# CherryMX.net
KiCad netlist of a schematic drawn in Altium Designer
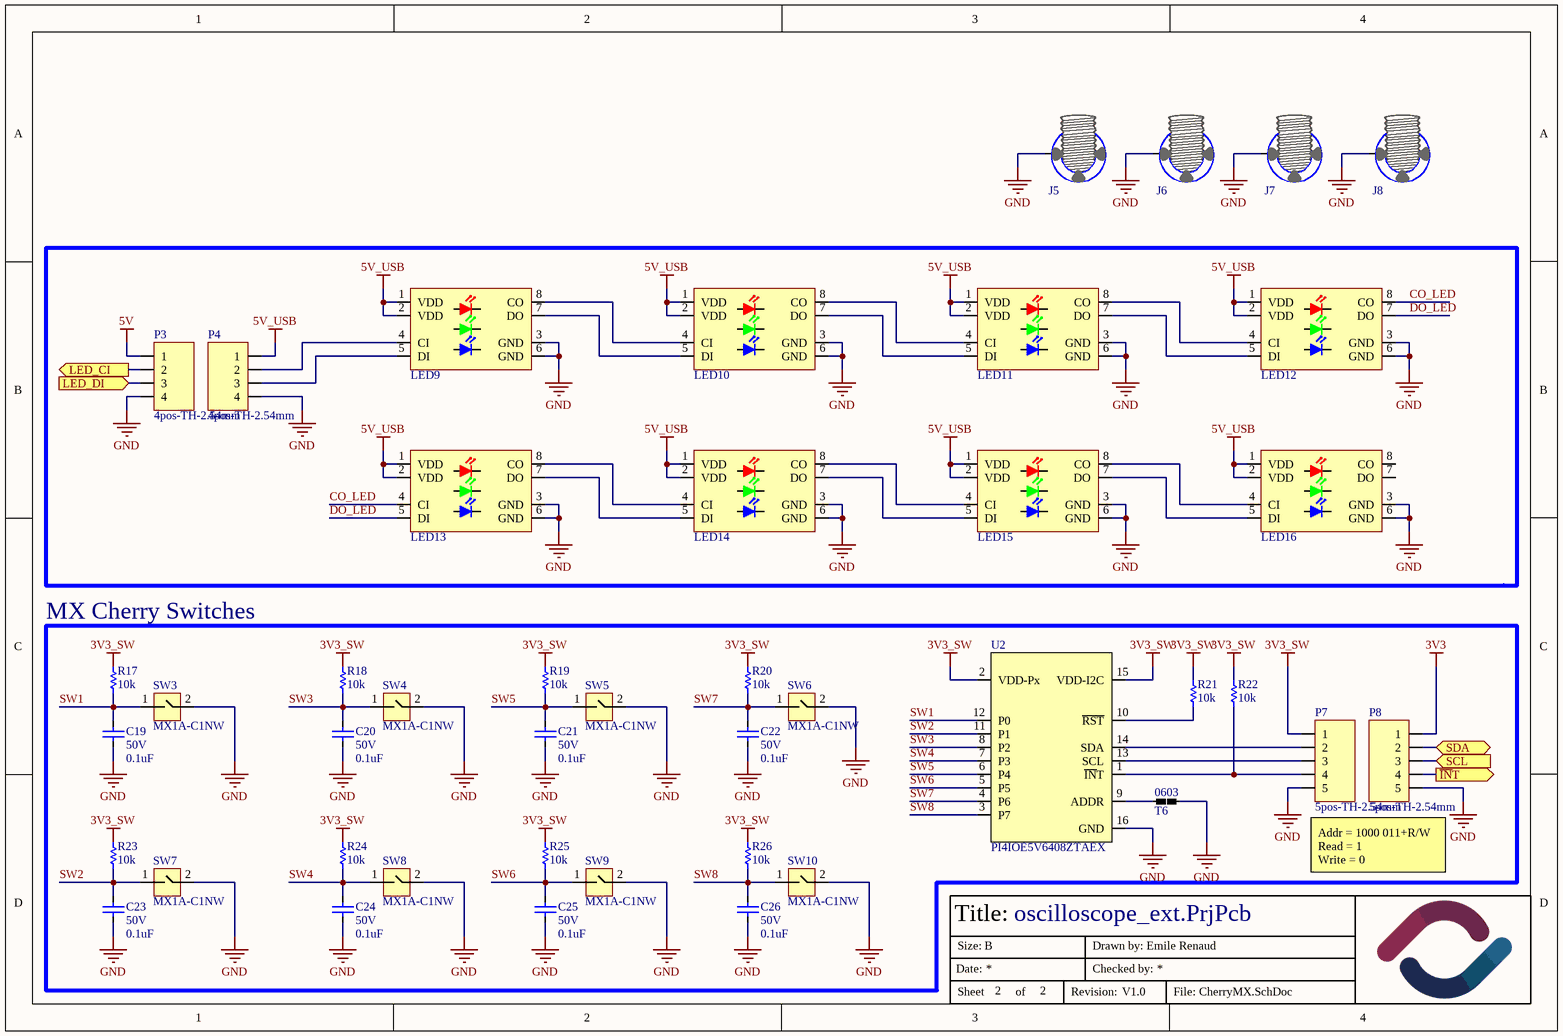
[diagram p0: CherryMX.SchDoc]

(export (version "E")
  (design (tool "Eeschema 10.0.6"))
  (components
    (comp (ref "C19")
      (value "0.1uF")
      (footprint "CAPACITOR-0603")
      (description "Capacitor-0603-0.1uF-50V-X7R")
      (fields (field (name "VOLT") "50V"))
      (libsource (lib "Capacitors") (part "Capacitor-0603-0.1uF-50V-X7R"))
    )
    (comp (ref "C20")
      (value "0.1uF")
      (footprint "CAPACITOR-0603")
      (description "Capacitor-0603-0.1uF-50V-X7R")
      (fields (field (name "VOLT") "50V"))
      (libsource (lib "Capacitors") (part "Capacitor-0603-0.1uF-50V-X7R"))
    )
    (comp (ref "C21")
      (value "0.1uF")
      (footprint "CAPACITOR-0603")
      (description "Capacitor-0603-0.1uF-50V-X7R")
      (fields (field (name "VOLT") "50V"))
      (libsource (lib "Capacitors") (part "Capacitor-0603-0.1uF-50V-X7R"))
    )
    (comp (ref "C22")
      (value "0.1uF")
      (footprint "CAPACITOR-0603")
      (description "Capacitor-0603-0.1uF-50V-X7R")
      (fields (field (name "VOLT") "50V"))
      (libsource (lib "Capacitors") (part "Capacitor-0603-0.1uF-50V-X7R"))
    )
    (comp (ref "C23")
      (value "0.1uF")
      (footprint "CAPACITOR-0603")
      (description "Capacitor-0603-0.1uF-50V-X7R")
      (fields (field (name "VOLT") "50V"))
      (libsource (lib "Capacitors") (part "Capacitor-0603-0.1uF-50V-X7R"))
    )
    (comp (ref "C24")
      (value "0.1uF")
      (footprint "CAPACITOR-0603")
      (description "Capacitor-0603-0.1uF-50V-X7R")
      (fields (field (name "VOLT") "50V"))
      (libsource (lib "Capacitors") (part "Capacitor-0603-0.1uF-50V-X7R"))
    )
    (comp (ref "C25")
      (value "0.1uF")
      (footprint "CAPACITOR-0603")
      (description "Capacitor-0603-0.1uF-50V-X7R")
      (fields (field (name "VOLT") "50V"))
      (libsource (lib "Capacitors") (part "Capacitor-0603-0.1uF-50V-X7R"))
    )
    (comp (ref "C26")
      (value "0.1uF")
      (footprint "CAPACITOR-0603")
      (description "Capacitor-0603-0.1uF-50V-X7R")
      (fields (field (name "VOLT") "50V"))
      (libsource (lib "Capacitors") (part "Capacitor-0603-0.1uF-50V-X7R"))
    )
    (comp (ref "J5")
      (value "hole")
      (footprint "HOLE-M2-Bolt")
      (description "Hole for M2 Bolt with 4mm pad")
      (libsource (lib "JumpersAndHoles") (part "Hole 2.3mm M2"))
    )
    (comp (ref "J6")
      (value "hole")
      (footprint "HOLE-M2-Bolt")
      (description "Hole for M2 Bolt with 4mm pad")
      (libsource (lib "JumpersAndHoles") (part "Hole 2.3mm M2"))
    )
    (comp (ref "J7")
      (value "hole")
      (footprint "HOLE-M2-Bolt")
      (description "Hole for M2 Bolt with 4mm pad")
      (libsource (lib "JumpersAndHoles") (part "Hole 2.3mm M2"))
    )
    (comp (ref "J8")
      (value "hole")
      (footprint "HOLE-M2-Bolt")
      (description "Hole for M2 Bolt with 4mm pad")
      (libsource (lib "JumpersAndHoles") (part "Hole 2.3mm M2"))
    )
    (comp (ref "LED9")
      (value "DotStar Micro")
      (footprint "LED_DOTSTAR")
      (libsource (lib "LEDs") (part "DotStar Micro"))
    )
    (comp (ref "LED10")
      (value "DotStar Micro")
      (footprint "LED_DOTSTAR")
      (libsource (lib "LEDs") (part "DotStar Micro"))
    )
    (comp (ref "LED11")
      (value "DotStar Micro")
      (footprint "LED_DOTSTAR")
      (libsource (lib "LEDs") (part "DotStar Micro"))
    )
    (comp (ref "LED12")
      (value "DotStar Micro")
      (footprint "LED_DOTSTAR")
      (libsource (lib "LEDs") (part "DotStar Micro"))
    )
    (comp (ref "LED13")
      (value "DotStar Micro")
      (footprint "LED_DOTSTAR")
      (libsource (lib "LEDs") (part "DotStar Micro"))
    )
    (comp (ref "LED14")
      (value "DotStar Micro")
      (footprint "LED_DOTSTAR")
      (libsource (lib "LEDs") (part "DotStar Micro"))
    )
    (comp (ref "LED15")
      (value "DotStar Micro")
      (footprint "LED_DOTSTAR")
      (libsource (lib "LEDs") (part "DotStar Micro"))
    )
    (comp (ref "LED16")
      (value "DotStar Micro")
      (footprint "LED_DOTSTAR")
      (libsource (lib "LEDs") (part "DotStar Micro"))
    )
    (comp (ref "P3")
      (value "4pos-TH-2.54mm")
      (footprint "HDR1X4")
      (description "4pos TH 2.54mm Header")
      (libsource (lib "") (part "4pos-TH-2.54mm_1"))
    )
    (comp (ref "P4")
      (value "4pos-TH-2.54mm")
      (footprint "HDR1X4")
      (description "4pos TH 2.54mm Header")
      (libsource (lib "Header") (part "4pos-TH-2.54mm"))
    )
    (comp (ref "P7")
      (value "5pos-TH-2.54mm")
      (footprint "HDR1X5")
      (description "5pos TH 2.54mm Header")
      (libsource (lib "") (part "5pos-TH-2.54mm_1"))
    )
    (comp (ref "P8")
      (value "5pos-TH-2.54mm")
      (footprint "HDR1X5")
      (description "5pos TH 2.54mm Header")
      (libsource (lib "Header") (part "5pos-TH-2.54mm"))
    )
    (comp (ref "R17")
      (value "10k")
      (footprint "Resistor-0603")
      (description "Resistor0603-10k")
      (fields (field (name "Comment") "SMT resistor"))
      (libsource (lib "Resistors") (part "Resistor0603-10k"))
    )
    (comp (ref "R18")
      (value "10k")
      (footprint "Resistor-0603")
      (description "Resistor0603-10k")
      (fields (field (name "Comment") "SMT resistor"))
      (libsource (lib "Resistors") (part "Resistor0603-10k"))
    )
    (comp (ref "R19")
      (value "10k")
      (footprint "Resistor-0603")
      (description "Resistor0603-10k")
      (fields (field (name "Comment") "SMT resistor"))
      (libsource (lib "Resistors") (part "Resistor0603-10k"))
    )
    (comp (ref "R20")
      (value "10k")
      (footprint "Resistor-0603")
      (description "Resistor0603-10k")
      (fields (field (name "Comment") "SMT resistor"))
      (libsource (lib "Resistors") (part "Resistor0603-10k"))
    )
    (comp (ref "R21")
      (value "10k")
      (footprint "Resistor-0603")
      (description "Resistor0603-10k")
      (fields (field (name "Comment") "SMT resistor"))
      (libsource (lib "Resistors") (part "Resistor0603-10k"))
    )
    (comp (ref "R22")
      (value "10k")
      (footprint "Resistor-0603")
      (description "Resistor0603-10k")
      (fields (field (name "Comment") "SMT resistor"))
      (libsource (lib "Resistors") (part "Resistor0603-10k"))
    )
    (comp (ref "R23")
      (value "10k")
      (footprint "Resistor-0603")
      (description "Resistor0603-10k")
      (fields (field (name "Comment") "SMT resistor"))
      (libsource (lib "Resistors") (part "Resistor0603-10k"))
    )
    (comp (ref "R24")
      (value "10k")
      (footprint "Resistor-0603")
      (description "Resistor0603-10k")
      (fields (field (name "Comment") "SMT resistor"))
      (libsource (lib "Resistors") (part "Resistor0603-10k"))
    )
    (comp (ref "R25")
      (value "10k")
      (footprint "Resistor-0603")
      (description "Resistor0603-10k")
      (fields (field (name "Comment") "SMT resistor"))
      (libsource (lib "Resistors") (part "Resistor0603-10k"))
    )
    (comp (ref "R26")
      (value "10k")
      (footprint "Resistor-0603")
      (description "Resistor0603-10k")
      (fields (field (name "Comment") "SMT resistor"))
      (libsource (lib "Resistors") (part "Resistor0603-10k"))
    )
    (comp (ref "SW3")
      (value "MX1A-C1NW")
      (footprint "MX2A-G1NB")
      (description "Pushbutton Switch SPST-NO Keyswitch Through Hole")
      (libsource (lib "Switches") (part "MX1A-C1NW"))
    )
    (comp (ref "SW4")
      (value "MX1A-C1NW")
      (footprint "MX2A-G1NB")
      (description "Pushbutton Switch SPST-NO Keyswitch Through Hole")
      (libsource (lib "Switches") (part "MX1A-C1NW"))
    )
    (comp (ref "SW5")
      (value "MX1A-C1NW")
      (footprint "MX2A-G1NB")
      (description "Pushbutton Switch SPST-NO Keyswitch Through Hole")
      (libsource (lib "Switches") (part "MX1A-C1NW"))
    )
    (comp (ref "SW6")
      (value "MX1A-C1NW")
      (footprint "MX2A-G1NB")
      (description "Pushbutton Switch SPST-NO Keyswitch Through Hole")
      (libsource (lib "Switches") (part "MX1A-C1NW"))
    )
    (comp (ref "SW7")
      (value "MX1A-C1NW")
      (footprint "MX2A-G1NB")
      (description "Pushbutton Switch SPST-NO Keyswitch Through Hole")
      (libsource (lib "Switches") (part "MX1A-C1NW"))
    )
    (comp (ref "SW8")
      (value "MX1A-C1NW")
      (footprint "MX2A-G1NB")
      (description "Pushbutton Switch SPST-NO Keyswitch Through Hole")
      (libsource (lib "Switches") (part "MX1A-C1NW"))
    )
    (comp (ref "SW9")
      (value "MX1A-C1NW")
      (footprint "MX2A-G1NB")
      (description "Pushbutton Switch SPST-NO Keyswitch Through Hole")
      (libsource (lib "Switches") (part "MX1A-C1NW"))
    )
    (comp (ref "SW10")
      (value "MX1A-C1NW")
      (footprint "MX2A-G1NB")
      (description "Pushbutton Switch SPST-NO Keyswitch Through Hole")
      (libsource (lib "Switches") (part "MX1A-C1NW"))
    )
    (comp (ref "T6")
      (value "NetTie_0603")
      (footprint "NetTie-0603-short")
      (libsource (lib "JumpersAndHoles") (part "NetTie_0603"))
    )
    (comp (ref "U2")
      (value "PI4IOE5V6408ZTAEX")
      (footprint "UQFN-16")
      (description "I/O Expander 8 I2C 1 MHz 16-UQFN (1.8x2.6)")
      (libsource (lib "IO-Expander") (part "PI4IOE5V6408ZTAEX"))
    )
  )
  (nets
    (net (code "1") (name "/CO_LED") (class "Default")
      (node (ref "LED12") (pin "8") (pinfunction "CO_8") (pintype "passive"))
      (node (ref "LED13") (pin "4") (pinfunction "CI_4") (pintype "passive"))
    )
    (net (code "2") (name "/DO_LED") (class "Default")
      (node (ref "LED12") (pin "7") (pinfunction "DO_7") (pintype "passive"))
      (node (ref "LED13") (pin "5") (pinfunction "DI_5") (pintype "passive"))
    )
    (net (code "3") (name "/LED_CI") (class "Default")
      (node (ref "P3") (pin "2") (pinfunction "2_2") (pintype "passive"))
    )
    (net (code "4") (name "/LED_DI") (class "Default")
      (node (ref "P3") (pin "3") (pinfunction "3_3") (pintype "passive"))
    )
    (net (code "5") (name "/SCL") (class "Default")
      (node (ref "P8") (pin "3") (pinfunction "3_3") (pintype "passive"))
    )
    (net (code "6") (name "/SDA") (class "Default")
      (node (ref "P8") (pin "2") (pinfunction "2_2") (pintype "passive"))
    )
    (net (code "7") (name "/SW1") (class "Default")
      (node (ref "C19") (pin "2") (pinfunction "2_2") (pintype "passive"))
      (node (ref "R17") (pin "1") (pinfunction "1_1") (pintype "passive"))
      (node (ref "SW3") (pin "1") (pinfunction "1_1") (pintype "passive"))
      (node (ref "U2") (pin "12") (pinfunction "P0_12") (pintype "passive"))
    )
    (net (code "8") (name "/SW2") (class "Default")
      (node (ref "C23") (pin "2") (pinfunction "2_2") (pintype "passive"))
      (node (ref "R23") (pin "1") (pinfunction "1_1") (pintype "passive"))
      (node (ref "SW7") (pin "1") (pinfunction "1_1") (pintype "passive"))
      (node (ref "U2") (pin "11") (pinfunction "P1_11") (pintype "passive"))
    )
    (net (code "9") (name "/SW3") (class "Default")
      (node (ref "C20") (pin "2") (pinfunction "2_2") (pintype "passive"))
      (node (ref "R18") (pin "1") (pinfunction "1_1") (pintype "passive"))
      (node (ref "SW4") (pin "1") (pinfunction "1_1") (pintype "passive"))
      (node (ref "U2") (pin "8") (pinfunction "P2_8") (pintype "passive"))
    )
    (net (code "10") (name "/SW4") (class "Default")
      (node (ref "C24") (pin "2") (pinfunction "2_2") (pintype "passive"))
      (node (ref "R24") (pin "1") (pinfunction "1_1") (pintype "passive"))
      (node (ref "SW8") (pin "1") (pinfunction "1_1") (pintype "passive"))
      (node (ref "U2") (pin "7") (pinfunction "P3_7") (pintype "passive"))
    )
    (net (code "11") (name "/SW5") (class "Default")
      (node (ref "C21") (pin "2") (pinfunction "2_2") (pintype "passive"))
      (node (ref "R19") (pin "1") (pinfunction "1_1") (pintype "passive"))
      (node (ref "SW5") (pin "1") (pinfunction "1_1") (pintype "passive"))
      (node (ref "U2") (pin "6") (pinfunction "P4_6") (pintype "passive"))
    )
    (net (code "12") (name "/SW6") (class "Default")
      (node (ref "C25") (pin "2") (pinfunction "2_2") (pintype "passive"))
      (node (ref "R25") (pin "1") (pinfunction "1_1") (pintype "passive"))
      (node (ref "SW9") (pin "1") (pinfunction "1_1") (pintype "passive"))
      (node (ref "U2") (pin "5") (pinfunction "P5_5") (pintype "passive"))
    )
    (net (code "13") (name "/SW7") (class "Default")
      (node (ref "C22") (pin "2") (pinfunction "2_2") (pintype "passive"))
      (node (ref "R20") (pin "1") (pinfunction "1_1") (pintype "passive"))
      (node (ref "SW6") (pin "1") (pinfunction "1_1") (pintype "passive"))
      (node (ref "U2") (pin "4") (pinfunction "P6_4") (pintype "passive"))
    )
    (net (code "14") (name "/SW8") (class "Default")
      (node (ref "C26") (pin "2") (pinfunction "2_2") (pintype "passive"))
      (node (ref "R26") (pin "1") (pinfunction "1_1") (pintype "passive"))
      (node (ref "SW10") (pin "1") (pinfunction "1_1") (pintype "passive"))
      (node (ref "U2") (pin "3") (pinfunction "P7_3") (pintype "passive"))
    )
    (net (code "15") (name "/~{IN}T") (class "Default")
      (node (ref "P8") (pin "4") (pinfunction "4_4") (pintype "passive"))
    )
    (net (code "16") (name "3V3") (class "Default")
      (node (ref "P8") (pin "1") (pinfunction "1_1") (pintype "passive"))
    )
    (net (code "17") (name "3V3_SW") (class "Default")
      (node (ref "P7") (pin "1") (pinfunction "1_1") (pintype "passive"))
      (node (ref "R17") (pin "2") (pinfunction "2_2") (pintype "passive"))
      (node (ref "R18") (pin "2") (pinfunction "2_2") (pintype "passive"))
      (node (ref "R19") (pin "2") (pinfunction "2_2") (pintype "passive"))
      (node (ref "R20") (pin "2") (pinfunction "2_2") (pintype "passive"))
      (node (ref "R21") (pin "2") (pinfunction "2_2") (pintype "passive"))
      (node (ref "R22") (pin "2") (pinfunction "2_2") (pintype "passive"))
      (node (ref "R23") (pin "2") (pinfunction "2_2") (pintype "passive"))
      (node (ref "R24") (pin "2") (pinfunction "2_2") (pintype "passive"))
      (node (ref "R25") (pin "2") (pinfunction "2_2") (pintype "passive"))
      (node (ref "R26") (pin "2") (pinfunction "2_2") (pintype "passive"))
      (node (ref "U2") (pin "15") (pinfunction "VDD-I2C_15") (pintype "passive"))
      (node (ref "U2") (pin "2") (pinfunction "VDD-Px_2") (pintype "passive"))
    )
    (net (code "18") (name "5V") (class "Default")
      (node (ref "P3") (pin "1") (pinfunction "1_1") (pintype "passive"))
    )
    (net (code "19") (name "5V_USB") (class "Default")
      (node (ref "LED10") (pin "1") (pinfunction "VDD_1") (pintype "passive"))
      (node (ref "LED10") (pin "2") (pinfunction "VDD_2") (pintype "passive"))
      (node (ref "LED11") (pin "1") (pinfunction "VDD_1") (pintype "passive"))
      (node (ref "LED11") (pin "2") (pinfunction "VDD_2") (pintype "passive"))
      (node (ref "LED12") (pin "1") (pinfunction "VDD_1") (pintype "passive"))
      (node (ref "LED12") (pin "2") (pinfunction "VDD_2") (pintype "passive"))
      (node (ref "LED13") (pin "1") (pinfunction "VDD_1") (pintype "passive"))
      (node (ref "LED13") (pin "2") (pinfunction "VDD_2") (pintype "passive"))
      (node (ref "LED14") (pin "1") (pinfunction "VDD_1") (pintype "passive"))
      (node (ref "LED14") (pin "2") (pinfunction "VDD_2") (pintype "passive"))
      (node (ref "LED15") (pin "1") (pinfunction "VDD_1") (pintype "passive"))
      (node (ref "LED15") (pin "2") (pinfunction "VDD_2") (pintype "passive"))
      (node (ref "LED16") (pin "1") (pinfunction "VDD_1") (pintype "passive"))
      (node (ref "LED16") (pin "2") (pinfunction "VDD_2") (pintype "passive"))
      (node (ref "LED9") (pin "1") (pinfunction "VDD_1") (pintype "passive"))
      (node (ref "LED9") (pin "2") (pinfunction "VDD_2") (pintype "passive"))
      (node (ref "P4") (pin "1") (pinfunction "1_1") (pintype "passive"))
    )
    (net (code "20") (name "GND") (class "Default")
      (node (ref "C19") (pin "1") (pinfunction "1_1") (pintype "passive"))
      (node (ref "C20") (pin "1") (pinfunction "1_1") (pintype "passive"))
      (node (ref "C21") (pin "1") (pinfunction "1_1") (pintype "passive"))
      (node (ref "C22") (pin "1") (pinfunction "1_1") (pintype "passive"))
      (node (ref "C23") (pin "1") (pinfunction "1_1") (pintype "passive"))
      (node (ref "C24") (pin "1") (pinfunction "1_1") (pintype "passive"))
      (node (ref "C25") (pin "1") (pinfunction "1_1") (pintype "passive"))
      (node (ref "C26") (pin "1") (pinfunction "1_1") (pintype "passive"))
      (node (ref "J5") (pin "1") (pinfunction "1_1") (pintype "passive"))
      (node (ref "J6") (pin "1") (pinfunction "1_1") (pintype "passive"))
      (node (ref "J7") (pin "1") (pinfunction "1_1") (pintype "passive"))
      (node (ref "J8") (pin "1") (pinfunction "1_1") (pintype "passive"))
      (node (ref "LED10") (pin "3") (pinfunction "GND_3") (pintype "passive"))
      (node (ref "LED10") (pin "6") (pinfunction "GND_6") (pintype "passive"))
      (node (ref "LED11") (pin "3") (pinfunction "GND_3") (pintype "passive"))
      (node (ref "LED11") (pin "6") (pinfunction "GND_6") (pintype "passive"))
      (node (ref "LED12") (pin "3") (pinfunction "GND_3") (pintype "passive"))
      (node (ref "LED12") (pin "6") (pinfunction "GND_6") (pintype "passive"))
      (node (ref "LED13") (pin "3") (pinfunction "GND_3") (pintype "passive"))
      (node (ref "LED13") (pin "6") (pinfunction "GND_6") (pintype "passive"))
      (node (ref "LED14") (pin "3") (pinfunction "GND_3") (pintype "passive"))
      (node (ref "LED14") (pin "6") (pinfunction "GND_6") (pintype "passive"))
      (node (ref "LED15") (pin "3") (pinfunction "GND_3") (pintype "passive"))
      (node (ref "LED15") (pin "6") (pinfunction "GND_6") (pintype "passive"))
      (node (ref "LED16") (pin "3") (pinfunction "GND_3") (pintype "passive"))
      (node (ref "LED16") (pin "6") (pinfunction "GND_6") (pintype "passive"))
      (node (ref "LED9") (pin "3") (pinfunction "GND_3") (pintype "passive"))
      (node (ref "LED9") (pin "6") (pinfunction "GND_6") (pintype "passive"))
      (node (ref "P3") (pin "4") (pinfunction "4_4") (pintype "passive"))
      (node (ref "P4") (pin "4") (pinfunction "4_4") (pintype "passive"))
      (node (ref "P7") (pin "5") (pinfunction "5_5") (pintype "passive"))
      (node (ref "P8") (pin "5") (pinfunction "5_5") (pintype "passive"))
      (node (ref "SW10") (pin "2") (pinfunction "2_2") (pintype "passive"))
      (node (ref "SW3") (pin "2") (pinfunction "2_2") (pintype "passive"))
      (node (ref "SW4") (pin "2") (pinfunction "2_2") (pintype "passive"))
      (node (ref "SW5") (pin "2") (pinfunction "2_2") (pintype "passive"))
      (node (ref "SW6") (pin "2") (pinfunction "2_2") (pintype "passive"))
      (node (ref "SW7") (pin "2") (pinfunction "2_2") (pintype "passive"))
      (node (ref "SW8") (pin "2") (pinfunction "2_2") (pintype "passive"))
      (node (ref "SW9") (pin "2") (pinfunction "2_2") (pintype "passive"))
      (node (ref "T6") (pin "1") (pinfunction "1_1") (pintype "passive"))
      (node (ref "U2") (pin "16") (pinfunction "GND_16") (pintype "passive"))
    )
    (net (code "21") (name "Net-(LED9-CI)") (class "Default")
      (node (ref "LED9") (pin "4") (pinfunction "CI_4") (pintype "passive"))
      (node (ref "P4") (pin "2") (pinfunction "2_2") (pintype "passive"))
    )
    (net (code "22") (name "Net-(LED9-DI)") (class "Default")
      (node (ref "LED9") (pin "5") (pinfunction "DI_5") (pintype "passive"))
      (node (ref "P4") (pin "3") (pinfunction "3_3") (pintype "passive"))
    )
    (net (code "23") (name "Net-(LED10-CI)") (class "Default")
      (node (ref "LED10") (pin "4") (pinfunction "CI_4") (pintype "passive"))
      (node (ref "LED9") (pin "8") (pinfunction "CO_8") (pintype "passive"))
    )
    (net (code "24") (name "Net-(LED10-CO)") (class "Default")
      (node (ref "LED10") (pin "8") (pinfunction "CO_8") (pintype "passive"))
      (node (ref "LED11") (pin "4") (pinfunction "CI_4") (pintype "passive"))
    )
    (net (code "25") (name "Net-(LED10-DI)") (class "Default")
      (node (ref "LED10") (pin "5") (pinfunction "DI_5") (pintype "passive"))
      (node (ref "LED9") (pin "7") (pinfunction "DO_7") (pintype "passive"))
    )
    (net (code "26") (name "Net-(LED10-DO)") (class "Default")
      (node (ref "LED10") (pin "7") (pinfunction "DO_7") (pintype "passive"))
      (node (ref "LED11") (pin "5") (pinfunction "DI_5") (pintype "passive"))
    )
    (net (code "27") (name "Net-(LED11-CO)") (class "Default")
      (node (ref "LED11") (pin "8") (pinfunction "CO_8") (pintype "passive"))
      (node (ref "LED12") (pin "4") (pinfunction "CI_4") (pintype "passive"))
    )
    (net (code "28") (name "Net-(LED11-DO)") (class "Default")
      (node (ref "LED11") (pin "7") (pinfunction "DO_7") (pintype "passive"))
      (node (ref "LED12") (pin "5") (pinfunction "DI_5") (pintype "passive"))
    )
    (net (code "29") (name "Net-(LED13-CO)") (class "Default")
      (node (ref "LED13") (pin "8") (pinfunction "CO_8") (pintype "passive"))
      (node (ref "LED14") (pin "4") (pinfunction "CI_4") (pintype "passive"))
    )
    (net (code "30") (name "Net-(LED13-DO)") (class "Default")
      (node (ref "LED13") (pin "7") (pinfunction "DO_7") (pintype "passive"))
      (node (ref "LED14") (pin "5") (pinfunction "DI_5") (pintype "passive"))
    )
    (net (code "31") (name "Net-(LED14-CO)") (class "Default")
      (node (ref "LED14") (pin "8") (pinfunction "CO_8") (pintype "passive"))
      (node (ref "LED15") (pin "4") (pinfunction "CI_4") (pintype "passive"))
    )
    (net (code "32") (name "Net-(LED14-DO)") (class "Default")
      (node (ref "LED14") (pin "7") (pinfunction "DO_7") (pintype "passive"))
      (node (ref "LED15") (pin "5") (pinfunction "DI_5") (pintype "passive"))
    )
    (net (code "33") (name "Net-(LED15-CO)") (class "Default")
      (node (ref "LED15") (pin "8") (pinfunction "CO_8") (pintype "passive"))
      (node (ref "LED16") (pin "4") (pinfunction "CI_4") (pintype "passive"))
    )
    (net (code "34") (name "Net-(LED15-DO)") (class "Default")
      (node (ref "LED15") (pin "7") (pinfunction "DO_7") (pintype "passive"))
      (node (ref "LED16") (pin "5") (pinfunction "DI_5") (pintype "passive"))
    )
    (net (code "35") (name "Net-(U2-ADDR)") (class "Default")
      (node (ref "T6") (pin "2") (pinfunction "2_2") (pintype "passive"))
      (node (ref "U2") (pin "9") (pinfunction "ADDR_9") (pintype "passive"))
    )
    (net (code "36") (name "Net-(U2-SCL)") (class "Default")
      (node (ref "P7") (pin "3") (pinfunction "3_3") (pintype "passive"))
      (node (ref "U2") (pin "13") (pinfunction "SCL_13") (pintype "passive"))
    )
    (net (code "37") (name "Net-(U2-SDA)") (class "Default")
      (node (ref "P7") (pin "2") (pinfunction "2_2") (pintype "passive"))
      (node (ref "U2") (pin "14") (pinfunction "SDA_14") (pintype "passive"))
    )
    (net (code "38") (name "Net-(U2-~{IN}T)") (class "Default")
      (node (ref "P7") (pin "4") (pinfunction "4_4") (pintype "passive"))
      (node (ref "R22") (pin "1") (pinfunction "1_1") (pintype "passive"))
      (node (ref "U2") (pin "1") (pinfunction "~{IN}T_1") (pintype "passive"))
    )
    (net (code "39") (name "Net-(U2-~{RST})") (class "Default")
      (node (ref "R21") (pin "1") (pinfunction "1_1") (pintype "passive"))
      (node (ref "U2") (pin "10") (pinfunction "~{RST}_10") (pintype "passive"))
    )
    (net (code "40") (name "unconnected-(LED16-CO-Pad8)") (class "Default")
      (node (ref "LED16") (pin "8") (pinfunction "CO_8") (pintype "passive"))
    )
    (net (code "41") (name "unconnected-(LED16-DO-Pad7)") (class "Default")
      (node (ref "LED16") (pin "7") (pinfunction "DO_7") (pintype "passive"))
    )
  )
)
